# MCU.net
KiCad netlist of a schematic drawn in Altium Designer
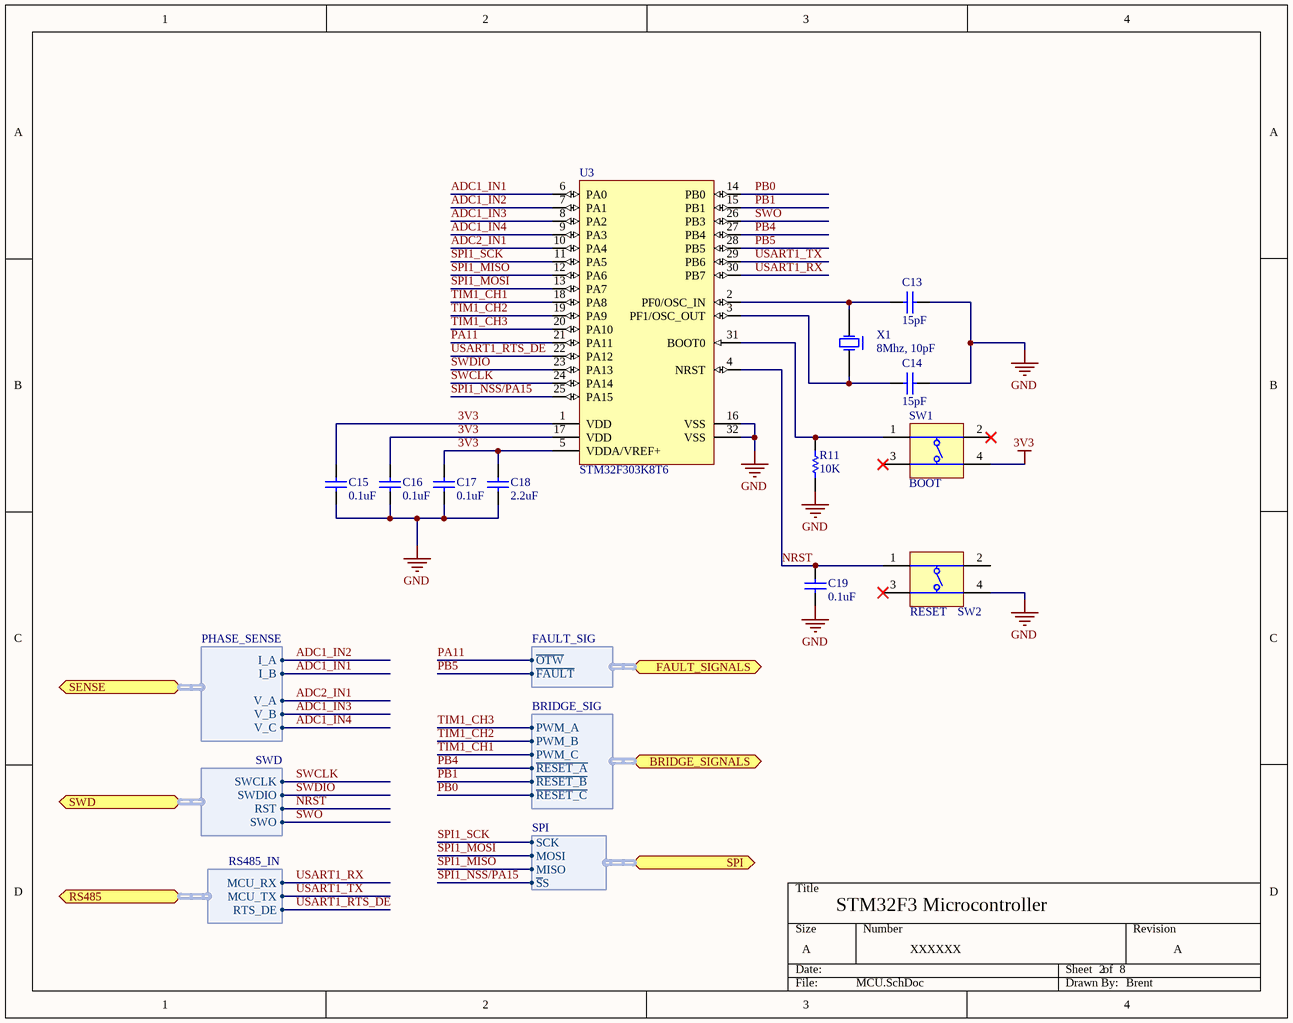
[diagram p0: MCU.SchDoc]

(export (version "E")
  (design (tool "Eeschema 10.0.6"))
  (components
    (comp (ref "C13")
      (value "15pF")
      (footprint "CAPC0603(1608)100_L")
      (description "CAP 15pF 25V ±1% 0603 (1608 Metric) Thickness 1mm SMD")
      (fields (field (name "TOLERANCE") "Â±1%"))
      (libsource (lib "Altium Content Vault") (part "CMP-1035-00674-1"))
    )
    (comp (ref "C14")
      (value "15pF")
      (footprint "CAPC0603(1608)100_L")
      (description "CAP 15pF 25V ±1% 0603 (1608 Metric) Thickness 1mm SMD")
      (fields (field (name "TOLERANCE") "Â±1%"))
      (libsource (lib "Altium Content Vault") (part "CMP-1035-00674-1"))
    )
    (comp (ref "C15")
      (value "0.1uF")
      (footprint "CAPC0603(1608)100_L")
      (description "CAP 100nF 100V ±10% 0603 (1608 Metric) Thickness 1mm SMD")
      (fields (field (name "TOLERANCE") "Â±10%"))
      (libsource (lib "Altium Content Vault") (part "CAP"))
    )
    (comp (ref "C16")
      (value "0.1uF")
      (footprint "CAPC0603(1608)100_L")
      (description "CAP 100nF 100V ±10% 0603 (1608 Metric) Thickness 1mm SMD")
      (fields (field (name "TOLERANCE") "Â±10%"))
      (libsource (lib "Altium Content Vault") (part "CAP"))
    )
    (comp (ref "C17")
      (value "0.1uF")
      (footprint "CAPC0603(1608)100_L")
      (description "CAP 100nF 100V ±10% 0603 (1608 Metric) Thickness 1mm SMD")
      (fields (field (name "TOLERANCE") "Â±10%"))
      (libsource (lib "Altium Content Vault") (part "CAP"))
    )
    (comp (ref "C18")
      (value "2.2uF")
      (footprint "CAPC0603(1608)100_L")
      (description "CAP 2.2uF 25V ±10% 0603 (1608 Metric) Thickness 1mm SMD")
      (fields (field (name "TOLERANCE") "Â±10%"))
      (libsource (lib "Altium Content Vault") (part "CMP-1035-02767-1"))
    )
    (comp (ref "C19")
      (value "0.1uF")
      (footprint "CAPC0603(1608)100_L")
      (description "CAP 100nF 100V ±10% 0603 (1608 Metric) Thickness 1mm SMD")
      (fields (field (name "TOLERANCE") "Â±10%"))
      (libsource (lib "Altium Content Vault") (part "CAP"))
    )
    (comp (ref "R11")
      (value "10K")
      (footprint "RESC0603(1608)_M")
      (description "10K 0.1W 1% 0603 (1608 Metric)  SMD")
      (fields (field (name "POWER") "0.1 W") (field (name "TOLERANCE") "1 %"))
      (libsource (lib "Altium Content Vault") (part "RES"))
    )
    (comp (ref "SW1")
      (value "BOOT")
      (footprint "SWITCH")
      (description "Switch, SPNO Push Button SMD")
      (fields (field (name "MANUFACTURER") "Diptronics") (field (name "PARTNUMBER") "DTSM-61NT/R"))
      (libsource (lib "altium-import") (part "root_0_DIPT-DTSM-6_"))
    )
    (comp (ref "SW2")
      (value "RESET")
      (footprint "SWITCH")
      (description "Switch, SPNO Push Button SMD")
      (fields (field (name "MANUFACTURER") "Diptronics") (field (name "PARTNUMBER") "DTSM-61NT/R"))
      (libsource (lib "altium-import") (part "root_0_DIPT-DTSM-6_"))
    )
    (comp (ref "U3")
      (value "STM32F303K8T6")
      (footprint "STM-LQFP32_M")
      (libsource (lib "Altium Content Vault") (part "CMP-0537-00040-1"))
    )
    (comp (ref "X1")
      (value "8Mhz, 10pF")
      (footprint "ABRA-ABM3B-4_V")
      (libsource (lib "Components") (part "ABRA-ABM3B-4"))
    )
  )
  (nets
    (net (code "7") (name "/ADC1_IN1") (class "Default")
      (node (ref "U3") (pin "6") (pinfunction "PA0_6") (pintype "bidirectional"))
    )
    (net (code "8") (name "/ADC1_IN2") (class "Default")
      (node (ref "U3") (pin "7") (pinfunction "PA1_7") (pintype "bidirectional"))
    )
    (net (code "9") (name "/ADC1_IN3") (class "Default")
      (node (ref "U3") (pin "8") (pinfunction "PA2_8") (pintype "bidirectional"))
    )
    (net (code "10") (name "/ADC1_IN4") (class "Default")
      (node (ref "U3") (pin "9") (pinfunction "PA3_9") (pintype "bidirectional"))
    )
    (net (code "11") (name "/ADC2_IN1") (class "Default")
      (node (ref "U3") (pin "10") (pinfunction "PA4_10") (pintype "bidirectional"))
    )
    (net (code "12") (name "/NRST") (class "Default")
      (node (ref "C19") (pin "2") (pinfunction "2_2") (pintype "passive"))
      (node (ref "SW2") (pin "1") (pinfunction "T1_1") (pintype "passive"))
      (node (ref "U3") (pin "4") (pinfunction "NRST_4") (pintype "bidirectional"))
    )
    (net (code "13") (name "/PA11") (class "Default")
      (node (ref "U3") (pin "21") (pinfunction "PA11_21") (pintype "bidirectional"))
    )
    (net (code "14") (name "/PB0") (class "Default")
      (node (ref "U3") (pin "14") (pinfunction "PB0_14") (pintype "bidirectional"))
    )
    (net (code "15") (name "/PB1") (class "Default")
      (node (ref "U3") (pin "15") (pinfunction "PB1_15") (pintype "bidirectional"))
    )
    (net (code "16") (name "/PB4") (class "Default")
      (node (ref "U3") (pin "27") (pinfunction "PB4_27") (pintype "bidirectional"))
    )
    (net (code "17") (name "/PB5") (class "Default")
      (node (ref "U3") (pin "28") (pinfunction "PB5_28") (pintype "bidirectional"))
    )
    (net (code "18") (name "/SPI1_MISO") (class "Default")
      (node (ref "U3") (pin "12") (pinfunction "PA6_12") (pintype "bidirectional"))
    )
    (net (code "19") (name "/SPI1_MOSI") (class "Default")
      (node (ref "U3") (pin "13") (pinfunction "PA7_13") (pintype "bidirectional"))
    )
    (net (code "20") (name "/SPI1_NSS{slash}PA15") (class "Default")
      (node (ref "U3") (pin "25") (pinfunction "PA15_25") (pintype "bidirectional"))
    )
    (net (code "21") (name "/SPI1_SCK") (class "Default")
      (node (ref "U3") (pin "11") (pinfunction "PA5_11") (pintype "bidirectional"))
    )
    (net (code "22") (name "/SWCLK") (class "Default")
      (node (ref "U3") (pin "24") (pinfunction "PA14_24") (pintype "bidirectional"))
    )
    (net (code "23") (name "/SWDIO") (class "Default")
      (node (ref "U3") (pin "23") (pinfunction "PA13_23") (pintype "bidirectional"))
    )
    (net (code "24") (name "/SWO") (class "Default")
      (node (ref "U3") (pin "26") (pinfunction "PB3_26") (pintype "bidirectional"))
    )
    (net (code "25") (name "/TIM1_CH1") (class "Default")
      (node (ref "U3") (pin "18") (pinfunction "PA8_18") (pintype "bidirectional"))
    )
    (net (code "26") (name "/TIM1_CH2") (class "Default")
      (node (ref "U3") (pin "19") (pinfunction "PA9_19") (pintype "bidirectional"))
    )
    (net (code "27") (name "/TIM1_CH3") (class "Default")
      (node (ref "U3") (pin "20") (pinfunction "PA10_20") (pintype "bidirectional"))
    )
    (net (code "28") (name "/USART1_RTS_DE") (class "Default")
      (node (ref "U3") (pin "22") (pinfunction "PA12_22") (pintype "bidirectional"))
    )
    (net (code "29") (name "/USART1_RX") (class "Default")
      (node (ref "U3") (pin "30") (pinfunction "PB7_30") (pintype "bidirectional"))
    )
    (net (code "30") (name "/USART1_TX") (class "Default")
      (node (ref "U3") (pin "29") (pinfunction "PB6_29") (pintype "bidirectional"))
    )
    (net (code "37") (name "3V3") (class "Default")
      (node (ref "C15") (pin "2") (pinfunction "2_2") (pintype "passive"))
      (node (ref "C16") (pin "2") (pinfunction "2_2") (pintype "passive"))
      (node (ref "C17") (pin "2") (pinfunction "2_2") (pintype "passive"))
      (node (ref "C18") (pin "1") (pinfunction "1_1") (pintype "passive"))
      (node (ref "SW1") (pin "4") (pinfunction "T3_4") (pintype "passive"))
      (node (ref "U3") (pin "1") (pinfunction "VDD_1") (pintype "power_in"))
      (node (ref "U3") (pin "17") (pinfunction "VDD_17") (pintype "power_in"))
      (node (ref "U3") (pin "5") (pinfunction "VDDA/VREF+_5") (pintype "power_in"))
    )
    (net (code "38") (name "GND") (class "Default")
      (node (ref "C13") (pin "2") (pinfunction "2_2") (pintype "passive"))
      (node (ref "C14") (pin "2") (pinfunction "2_2") (pintype "passive"))
      (node (ref "C15") (pin "1") (pinfunction "1_1") (pintype "passive"))
      (node (ref "C16") (pin "1") (pinfunction "1_1") (pintype "passive"))
      (node (ref "C17") (pin "1") (pinfunction "1_1") (pintype "passive"))
      (node (ref "C18") (pin "2") (pinfunction "2_2") (pintype "passive"))
      (node (ref "C19") (pin "1") (pinfunction "1_1") (pintype "passive"))
      (node (ref "R11") (pin "1") (pinfunction "1_1") (pintype "passive"))
      (node (ref "SW2") (pin "4") (pinfunction "T3_4") (pintype "passive"))
      (node (ref "U3") (pin "16") (pinfunction "VSS_16") (pintype "power_in"))
      (node (ref "U3") (pin "32") (pinfunction "VSS_32") (pintype "power_in"))
    )
    (net (code "39") (name "Net-(SW1-T1)") (class "Default")
      (node (ref "R11") (pin "2") (pinfunction "2_2") (pintype "passive"))
      (node (ref "SW1") (pin "1") (pinfunction "T1_1") (pintype "passive"))
      (node (ref "U3") (pin "31") (pinfunction "BOOT0_31") (pintype "input"))
    )
    (net (code "40") (name "Net-(U3-PF0{slash}OSC_IN)") (class "Default")
      (node (ref "C13") (pin "1") (pinfunction "1_1") (pintype "passive"))
      (node (ref "U3") (pin "2") (pinfunction "PF0/OSC_IN_2") (pintype "bidirectional"))
      (node (ref "X1") (pin "3") (pinfunction "X2_3") (pintype "passive"))
    )
    (net (code "41") (name "Net-(U3-PF1{slash}OSC_OUT)") (class "Default")
      (node (ref "C14") (pin "1") (pinfunction "1_1") (pintype "passive"))
      (node (ref "U3") (pin "3") (pinfunction "PF1/OSC_OUT_3") (pintype "bidirectional"))
      (node (ref "X1") (pin "1") (pinfunction "X1_1") (pintype "passive"))
    )
    (net (code "42") (name "unconnected-(SW1-T2-Pad2)") (class "Default")
      (node (ref "SW1") (pin "2") (pinfunction "T2_2") (pintype "passive+no_connect"))
    )
    (net (code "43") (name "unconnected-(SW1-T3-Pad3)") (class "Default")
      (node (ref "SW1") (pin "3") (pinfunction "T3_3") (pintype "passive+no_connect"))
    )
    (net (code "44") (name "unconnected-(SW2-T2-Pad2)") (class "Default")
      (node (ref "SW2") (pin "2") (pinfunction "T2_2") (pintype "passive"))
    )
    (net (code "45") (name "unconnected-(SW2-T3-Pad3)") (class "Default")
      (node (ref "SW2") (pin "3") (pinfunction "T3_3") (pintype "passive+no_connect"))
    )
    (net (code "46") (name "unconnected-(X1-Pad2)") (class "Default")
      (node (ref "X1") (pin "2") (pinfunction "2_2") (pintype "passive"))
    )
  )
)
